# Power.net
KiCad netlist of a schematic drawn in Altium Designer
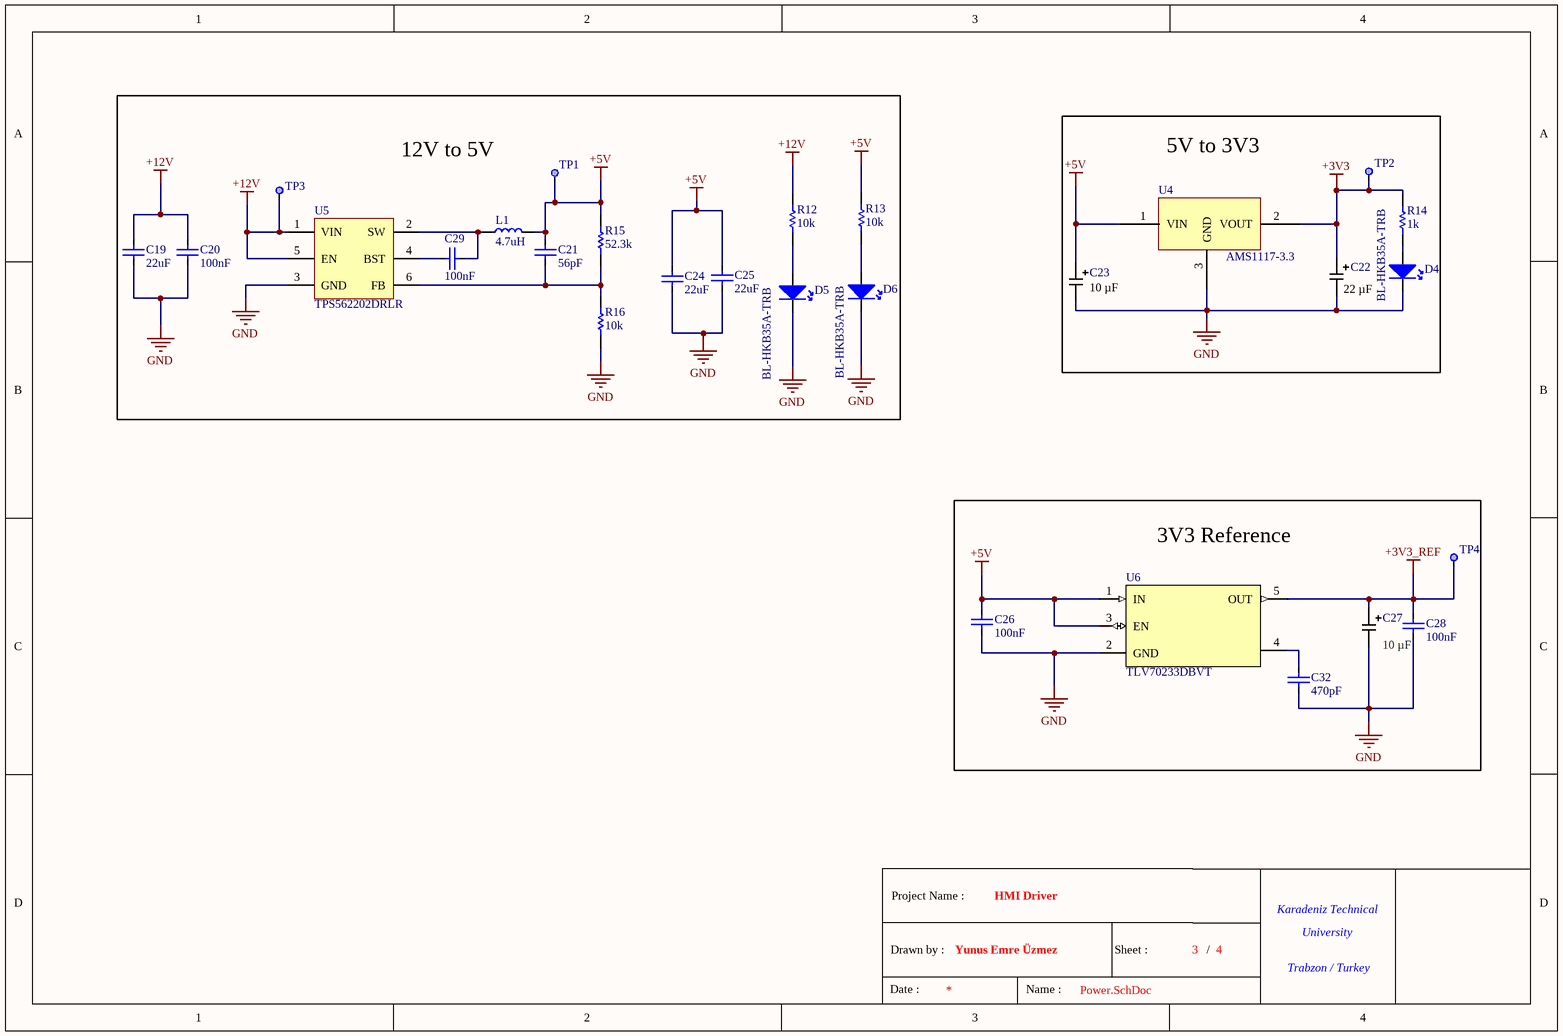
[diagram p0: Power.SchDoc]

(export (version "E")
  (design (tool "Eeschema 10.0.6"))
  (components
    (comp (ref "C19")
      (value "22uF")
      (footprint "CAP-1210")
      (fields
        (field (name "MANUFACTURER") "Samsung Electro-Mechanics")
        (field (name "VOLTAGE") "25V")
        (field (name "TOLERANCE") "%10")
      )
      (libsource (lib "Motor_Driver") (part "CL32B226KAJNNNE"))
    )
    (comp (ref "C20")
      (value "100nF")
      (footprint "CAP-0603")
      (fields
        (field (name "MANUFACTURER") "TDK")
        (field (name "VOLTAGE") "50V")
        (field (name "TOLERANCE") "%10")
      )
      (libsource (lib "Motor_Driver") (part "CGA3E2X7R1H104K080AA"))
    )
    (comp (ref "C21")
      (value "56pF")
      (footprint "Motor_Driver:CAP-0603")
      (fields
        (field (name "MANUFACTURER") "Murata")
        (field (name "TOLERANCE") "%1")
        (field (name "VOLTAGE") "100V")
      )
      (libsource (lib "My_Libs") (part "GCM1885C2A560FA16D"))
    )
    (comp (ref "C22")
      (value "T491B226K020AT")
      (footprint "KEMET_CAP_TAN-B")
      (description "CAP TANT 22UF 10% 20V 1411")
      (fields
        (field (name "MANUFACTURER") "KEMET")
        (field (name "TOLERANCE") "±10%")
        (field (name "CAPACITANCE") "22 µF")
      )
      (libsource (lib "Tantalum Capacitors") (part "T491B226K020AT"))
    )
    (comp (ref "C23")
      (value "T491B106M016AT")
      (footprint "KEMET_CAP_TAN-B")
      (description "CAP TANT 10UF 20% 16V 1411")
      (fields
        (field (name "MANUFACTURER") "KEMET")
        (field (name "TOLERANCE") "±20%")
        (field (name "CAPACITANCE") "10 µF")
      )
      (libsource (lib "Tantalum Capacitors") (part "T491B106M016AT"))
    )
    (comp (ref "C24")
      (value "22uF")
      (footprint "CAP-1210")
      (fields
        (field (name "MANUFACTURER") "Samsung Electro-Mechanics")
        (field (name "VOLTAGE") "25V")
        (field (name "TOLERANCE") "%10")
      )
      (libsource (lib "Motor_Driver") (part "CL32B226KAJNNNE"))
    )
    (comp (ref "C25")
      (value "22uF")
      (footprint "CAP-1210")
      (fields
        (field (name "MANUFACTURER") "Samsung Electro-Mechanics")
        (field (name "VOLTAGE") "25V")
        (field (name "TOLERANCE") "%10")
      )
      (libsource (lib "Motor_Driver") (part "CL32B226KAJNNNE"))
    )
    (comp (ref "C26")
      (value "100nF")
      (footprint "CAP-0603")
      (fields
        (field (name "MANUFACTURER") "TDK")
        (field (name "VOLTAGE") "50V")
        (field (name "TOLERANCE") "%10")
      )
      (libsource (lib "Motor_Driver") (part "CGA3E2X7R1H104K080AA"))
    )
    (comp (ref "C27")
      (value "T491B106M016AT")
      (footprint "KEMET_CAP_TAN-B")
      (description "CAP TANT 10UF 20% 16V 1411")
      (fields
        (field (name "MANUFACTURER") "KEMET")
        (field (name "TOLERANCE") "±20%")
        (field (name "CAPACITANCE") "10 µF")
      )
      (libsource (lib "Tantalum Capacitors") (part "T491B106M016AT"))
    )
    (comp (ref "C28")
      (value "100nF")
      (footprint "CAP-0603")
      (fields
        (field (name "MANUFACTURER") "TDK")
        (field (name "VOLTAGE") "50V")
        (field (name "TOLERANCE") "%10")
      )
      (libsource (lib "Motor_Driver") (part "CGA3E2X7R1H104K080AA"))
    )
    (comp (ref "C29")
      (value "100nF")
      (footprint "CAP-0603")
      (fields
        (field (name "MANUFACTURER") "TDK")
        (field (name "VOLTAGE") "50V")
        (field (name "TOLERANCE") "%10")
      )
      (libsource (lib "Motor_Driver") (part "CGA3E2X7R1H104K080AA"))
    )
    (comp (ref "C32")
      (value "470pF")
      (footprint "CAP-0603")
      (fields
        (field (name "VOLTAGE") "50V")
        (field (name "TOLERANCE") "%10")
        (field (name "MANUFACTURER") "Samsung")
      )
      (libsource (lib "jl_lib") (part "CL10B471KB8NNNC"))
    )
    (comp (ref "D4")
      (value "BL-HKB35A-TRB")
      (footprint "LED-0805")
      (fields (field (name "MANUFACTURER") "BRIGHT LED"))
      (libsource (lib "Motor_Driver") (part "BL-HKB35A-TRB"))
    )
    (comp (ref "D5")
      (value "BL-HKB35A-TRB")
      (footprint "LED-0805")
      (fields (field (name "MANUFACTURER") "BRIGHT LED"))
      (libsource (lib "Motor_Driver") (part "BL-HKB35A-TRB"))
    )
    (comp (ref "D6")
      (value "BL-HKB35A-TRB")
      (footprint "LED-0805")
      (fields (field (name "MANUFACTURER") "BRIGHT LED"))
      (libsource (lib "Motor_Driver") (part "BL-HKB35A-TRB"))
    )
    (comp (ref "L1")
      (value "4.7uH")
      (footprint "Motor_Driver:IND_EATON_DR125-4R7-R")
      (fields (field (name "MANUFACTURER") "Eaton") (field (name "TOLERANCE") "%20"))
      (libsource (lib "My_Libs") (part "DR125-4R7-R"))
    )
    (comp (ref "R12")
      (value "10k")
      (footprint "Motor_Driver:RES-0603")
      (fields
        (field (name "MANUFACTURER") "Vishay")
        (field (name "TOLERANCE") "%1")
        (field (name "POWER") "0.1W")
      )
      (libsource (lib "My_Libs") (part "CRCW060310K0FKEA"))
    )
    (comp (ref "R13")
      (value "10k")
      (footprint "Motor_Driver:RES-0603")
      (fields
        (field (name "MANUFACTURER") "Vishay")
        (field (name "TOLERANCE") "%1")
        (field (name "POWER") "0.1W")
      )
      (libsource (lib "My_Libs") (part "CRCW060310K0FKEA"))
    )
    (comp (ref "R14")
      (value "1k")
      (footprint "Motor_Driver:RES-0603")
      (fields
        (field (name "MANUFACTURER") "Vishay")
        (field (name "TOLERANCE") "%1")
        (field (name "POWER") "0.1W")
      )
      (libsource (lib "My_Libs") (part "CRCW06031K00FKEAC"))
    )
    (comp (ref "R15")
      (value "52.3k")
      (footprint "Motor_Driver:RES-0603")
      (fields
        (field (name "MANUFACTURER") "Panasonic")
        (field (name "TOLERANCE") "%1")
        (field (name "POWER") "0.1W")
      )
      (libsource (lib "My_Libs") (part "ERJ-3EKF5232V"))
    )
    (comp (ref "R16")
      (value "10k")
      (footprint "Motor_Driver:RES-0603")
      (fields
        (field (name "MANUFACTURER") "Vishay")
        (field (name "TOLERANCE") "%1")
        (field (name "POWER") "0.1W")
      )
      (libsource (lib "My_Libs") (part "CRCW060310K0FKEA"))
    )
    (comp (ref "TP1")
      (value "Test Point")
      (footprint "0.8mm Test Point")
      (libsource (lib "Motor_Driver") (part "Test Point"))
    )
    (comp (ref "TP2")
      (value "Test Point")
      (footprint "0.8mm Test Point")
      (libsource (lib "Motor_Driver") (part "Test Point"))
    )
    (comp (ref "TP3")
      (value "Test Point")
      (footprint "0.8mm Test Point")
      (libsource (lib "Motor_Driver") (part "Test Point"))
    )
    (comp (ref "TP4")
      (value "Test Point")
      (footprint "0.8mm Test Point")
      (libsource (lib "Motor_Driver") (part "Test Point"))
    )
    (comp (ref "U4")
      (value "AMS1117-3.3")
      (footprint "SOT-223")
      (fields (field (name "MANUFACTURER") "Monolithic"))
      (libsource (lib "jl_lib") (part "AMS1117-3.3"))
    )
    (comp (ref "U5")
      (value "TPS562202DRLR")
      (footprint "SOT-563")
      (fields (field (name "MANUFACTURER") "Texas Instruments"))
      (libsource (lib "Motor_Driver") (part "TPS562202DRLR"))
    )
    (comp (ref "U6")
      (value "TLV70233DBVT")
      (footprint "SOT23-5")
      (fields (field (name "MANUFACTURER") "TEXAS") (field (name "VOLTAGE") "3.3V"))
      (libsource (lib "jl_lib") (part "TLV70233DBVT"))
    )
  )
  (nets
    (net (code "1") (name "+3V3") (class "Default")
      (node (ref "C22") (pin "1") (pinfunction "1_1") (pintype "passive"))
      (node (ref "R14") (pin "1") (pinfunction "1_1") (pintype "passive"))
      (node (ref "TP2") (pin "1") (pinfunction "1_1") (pintype "passive"))
      (node (ref "U4") (pin "2") (pinfunction "VOUT_2") (pintype "passive"))
    )
    (net (code "2") (name "+3V3_REF") (class "Default")
      (node (ref "C27") (pin "1") (pinfunction "1_1") (pintype "passive"))
      (node (ref "C28") (pin "2") (pinfunction "2_2") (pintype "passive"))
      (node (ref "TP4") (pin "1") (pinfunction "1_1") (pintype "passive"))
      (node (ref "U6") (pin "5") (pinfunction "OUT_5") (pintype "output"))
    )
    (net (code "3") (name "+5V") (class "Default")
      (node (ref "C21") (pin "2") (pinfunction "2_2") (pintype "passive"))
      (node (ref "C23") (pin "1") (pinfunction "1_1") (pintype "passive"))
      (node (ref "C24") (pin "2") (pinfunction "2_2") (pintype "passive"))
      (node (ref "C25") (pin "2") (pinfunction "2_2") (pintype "passive"))
      (node (ref "C26") (pin "2") (pinfunction "2_2") (pintype "passive"))
      (node (ref "L1") (pin "2") (pinfunction "2_2") (pintype "passive"))
      (node (ref "R13") (pin "2") (pinfunction "2_2") (pintype "passive"))
      (node (ref "R15") (pin "2") (pinfunction "2_2") (pintype "passive"))
      (node (ref "TP1") (pin "1") (pinfunction "1_1") (pintype "passive"))
      (node (ref "U4") (pin "1") (pinfunction "VIN_1") (pintype "passive"))
      (node (ref "U6") (pin "1") (pinfunction "IN_1") (pintype "input"))
      (node (ref "U6") (pin "3") (pinfunction "EN_3") (pintype "bidirectional"))
    )
    (net (code "4") (name "+12V") (class "Default")
      (node (ref "C19") (pin "2") (pinfunction "2_2") (pintype "passive"))
      (node (ref "C20") (pin "2") (pinfunction "2_2") (pintype "passive"))
      (node (ref "R12") (pin "2") (pinfunction "2_2") (pintype "passive"))
      (node (ref "TP3") (pin "1") (pinfunction "1_1") (pintype "passive"))
      (node (ref "U5") (pin "1") (pinfunction "VIN_1") (pintype "passive"))
      (node (ref "U5") (pin "5") (pinfunction "EN_5") (pintype "passive"))
    )
    (net (code "5") (name "GND") (class "Default")
      (node (ref "C19") (pin "1") (pinfunction "1_1") (pintype "passive"))
      (node (ref "C20") (pin "1") (pinfunction "1_1") (pintype "passive"))
      (node (ref "C22") (pin "2") (pinfunction "2_2") (pintype "passive"))
      (node (ref "C23") (pin "2") (pinfunction "2_2") (pintype "passive"))
      (node (ref "C24") (pin "1") (pinfunction "1_1") (pintype "passive"))
      (node (ref "C25") (pin "1") (pinfunction "1_1") (pintype "passive"))
      (node (ref "C26") (pin "1") (pinfunction "1_1") (pintype "passive"))
      (node (ref "C27") (pin "2") (pinfunction "2_2") (pintype "passive"))
      (node (ref "C28") (pin "1") (pinfunction "1_1") (pintype "passive"))
      (node (ref "C32") (pin "1") (pinfunction "1_1") (pintype "passive"))
      (node (ref "D4") (pin "2") (pinfunction "K_2") (pintype "passive"))
      (node (ref "D5") (pin "2") (pinfunction "K_2") (pintype "passive"))
      (node (ref "D6") (pin "2") (pinfunction "K_2") (pintype "passive"))
      (node (ref "R16") (pin "1") (pinfunction "1_1") (pintype "passive"))
      (node (ref "U4") (pin "3") (pinfunction "GND_3") (pintype "passive"))
      (node (ref "U5") (pin "3") (pinfunction "GND_3") (pintype "passive"))
      (node (ref "U6") (pin "2") (pinfunction "GND_2") (pintype "power_in"))
    )
    (net (code "6") (name "Net-(C32-Pad2)") (class "Default")
      (node (ref "C32") (pin "2") (pinfunction "2_2") (pintype "passive"))
      (node (ref "U6") (pin "4") (pintype "power_in"))
    )
    (net (code "7") (name "Net-(D4-A)") (class "Default")
      (node (ref "D4") (pin "1") (pinfunction "A_1") (pintype "passive"))
      (node (ref "R14") (pin "2") (pinfunction "2_2") (pintype "passive"))
    )
    (net (code "8") (name "Net-(D5-A)") (class "Default")
      (node (ref "D5") (pin "1") (pinfunction "A_1") (pintype "passive"))
      (node (ref "R12") (pin "1") (pinfunction "1_1") (pintype "passive"))
    )
    (net (code "9") (name "Net-(D6-A)") (class "Default")
      (node (ref "D6") (pin "1") (pinfunction "A_1") (pintype "passive"))
      (node (ref "R13") (pin "1") (pinfunction "1_1") (pintype "passive"))
    )
    (net (code "10") (name "Net-(U5-BST)") (class "Default")
      (node (ref "C29") (pin "2") (pinfunction "2_2") (pintype "passive"))
      (node (ref "U5") (pin "4") (pinfunction "BST_4") (pintype "passive"))
    )
    (net (code "11") (name "Net-(U5-FB)") (class "Default")
      (node (ref "C21") (pin "1") (pinfunction "1_1") (pintype "passive"))
      (node (ref "R15") (pin "1") (pinfunction "1_1") (pintype "passive"))
      (node (ref "R16") (pin "2") (pinfunction "2_2") (pintype "passive"))
      (node (ref "U5") (pin "6") (pinfunction "FB_6") (pintype "passive"))
    )
    (net (code "12") (name "Net-(U5-SW)") (class "Default")
      (node (ref "C29") (pin "1") (pinfunction "1_1") (pintype "passive"))
      (node (ref "L1") (pin "1") (pinfunction "1_1") (pintype "passive"))
      (node (ref "U5") (pin "2") (pinfunction "SW_2") (pintype "passive"))
    )
  )
)
